# FX-50FHii_gameboy_Project.net
KiCad netlist of a schematic drawn in EasyEDA Pro
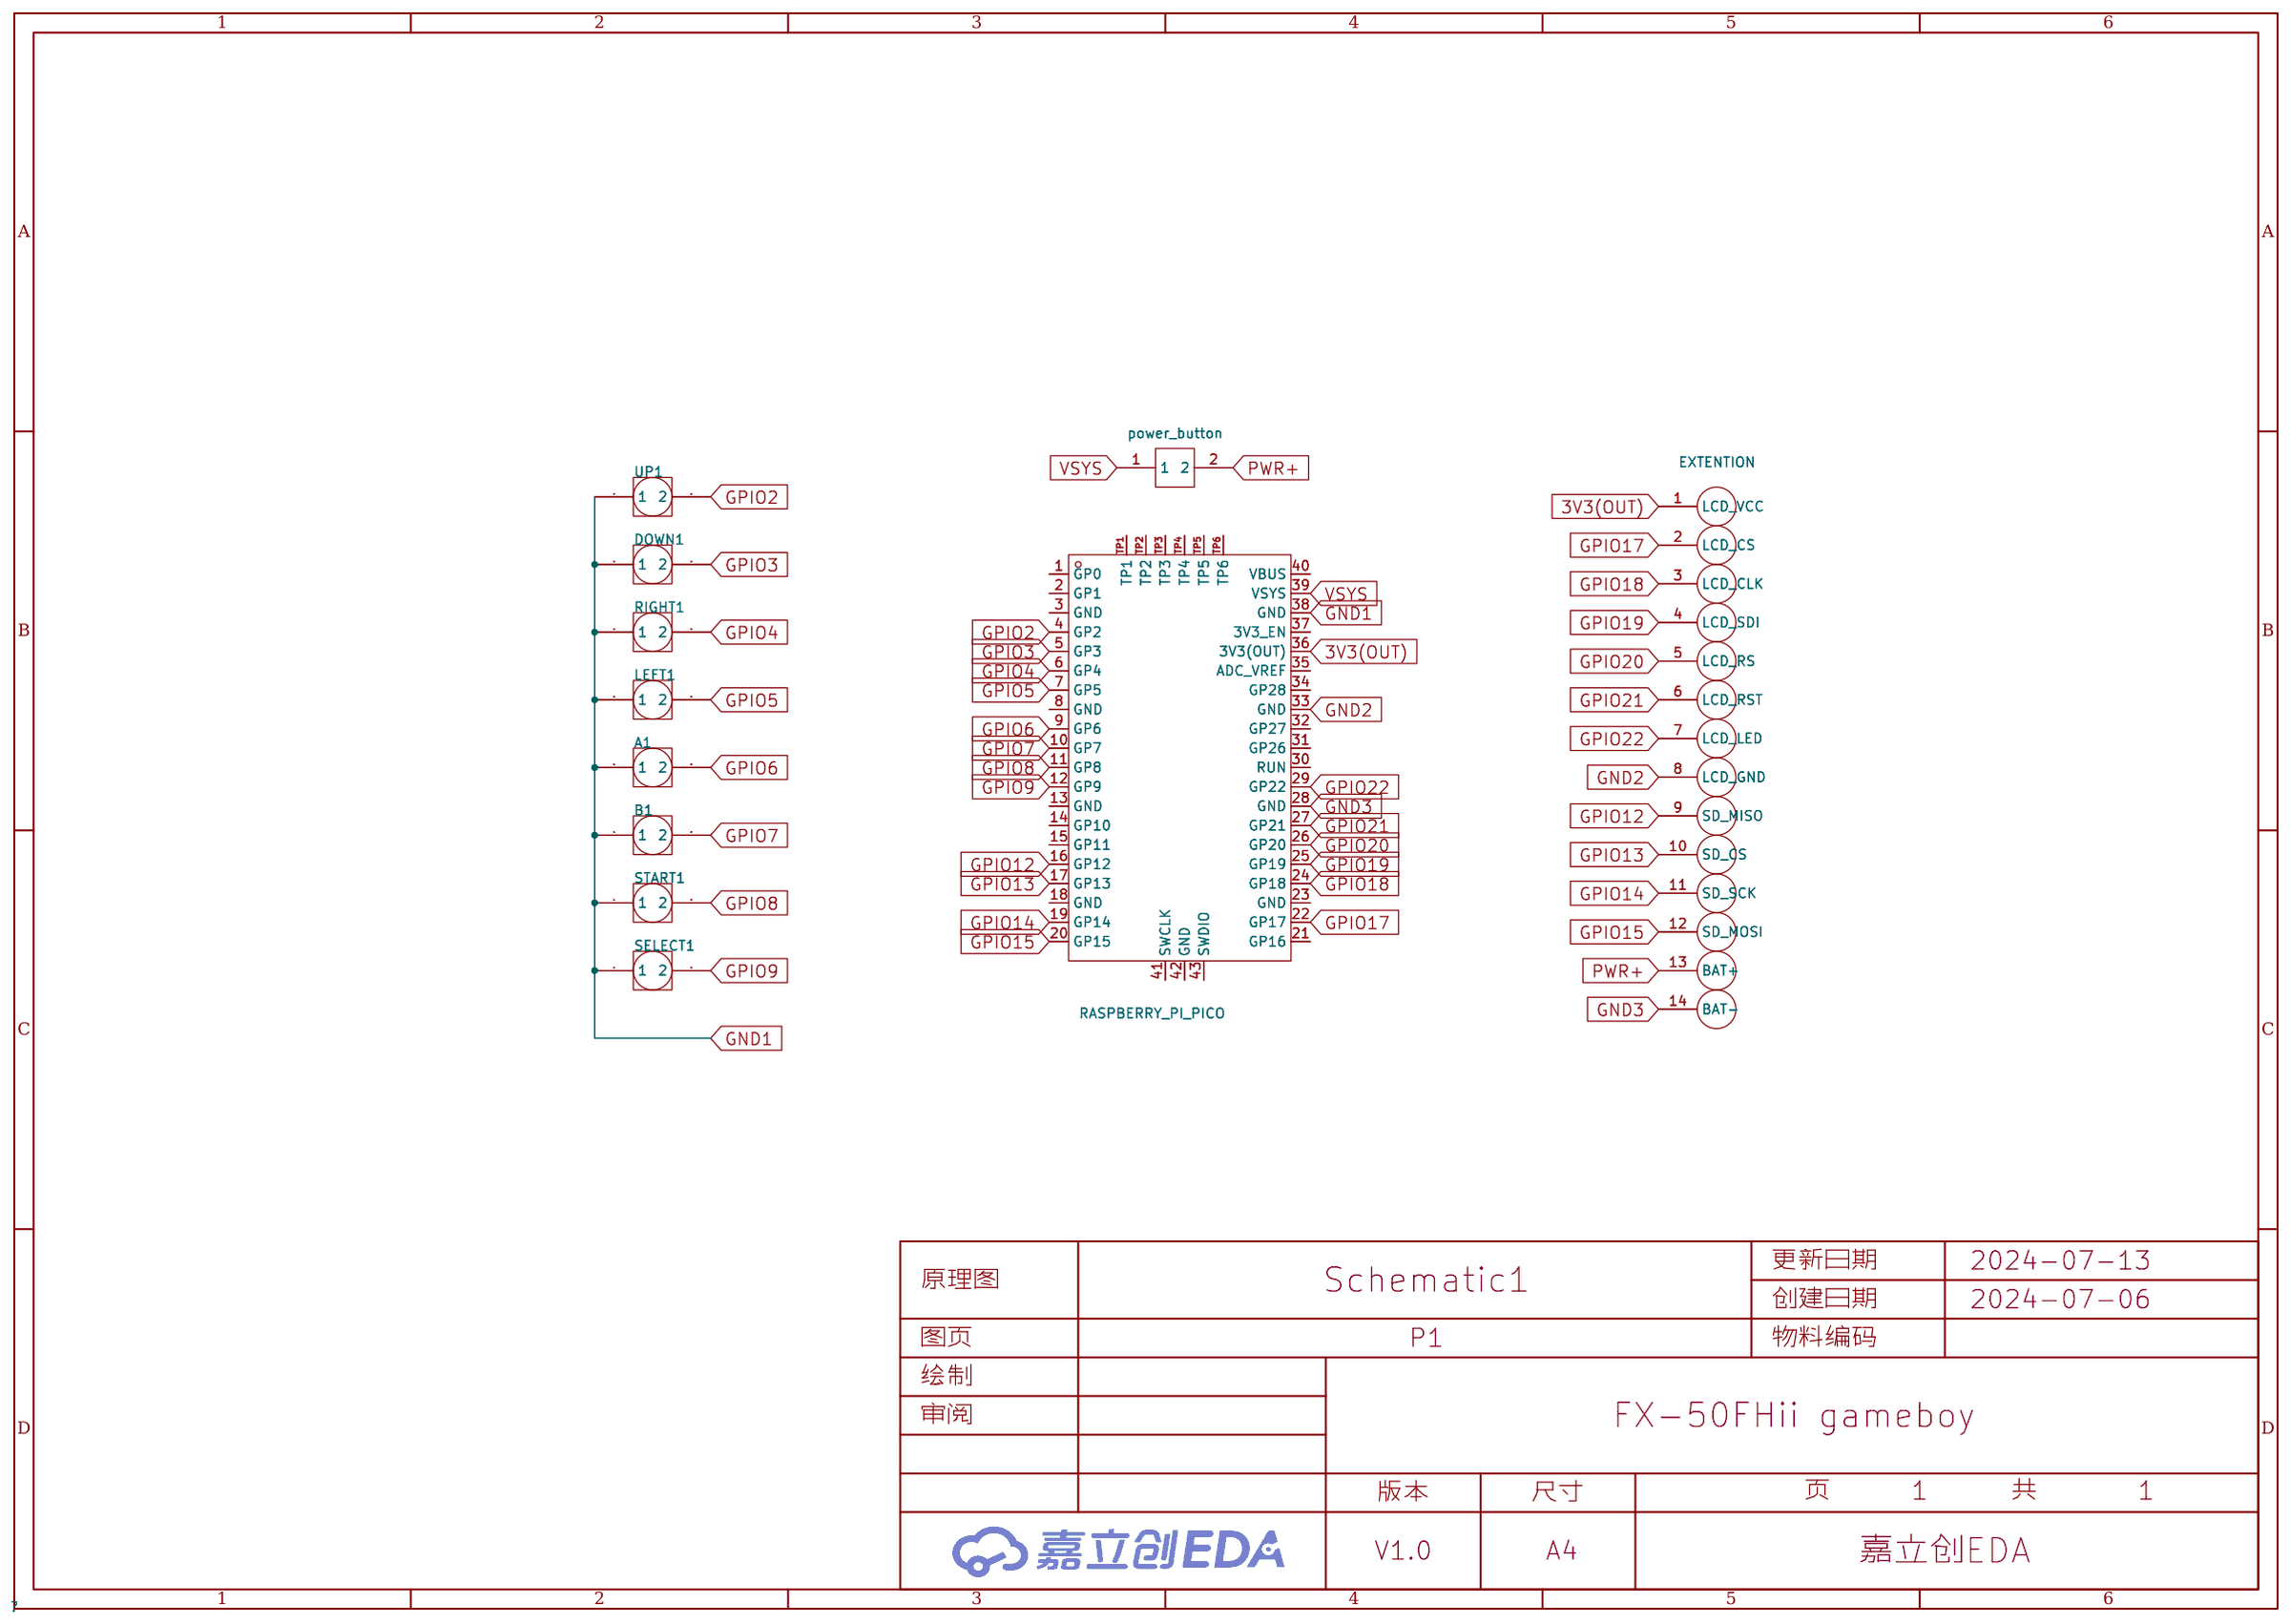
[diagram p0: schematic sheet]

(export (version "E")
  (design (tool "Eeschema 10.0.6"))
  (components
    (comp (ref "A1") (value "~") (footprint "easyedapro:锅仔按键") (libsource (lib "easyedapro") (part "导电胶触点")))
    (comp (ref "B1") (value "~") (footprint "easyedapro:锅仔按键") (libsource (lib "easyedapro") (part "导电胶触点")))
    (comp (ref "DOWN1")
      (value "~")
      (footprint "easyedapro:锅仔按键")
      (libsource (lib "easyedapro") (part "导电胶触点"))
    )
    (comp (ref "EXTENTION")
      (value "~")
      (footprint "easyedapro:CN1")
      (libsource (lib "easyedapro") (part "焊盤"))
    )
    (comp (ref "LEFT1")
      (value "~")
      (footprint "easyedapro:锅仔按键")
      (libsource (lib "easyedapro") (part "导电胶触点"))
    )
    (comp (ref "power_button")
      (value "~")
      (footprint "easyedapro:自動鎖住的按鈕")
      (libsource (lib "easyedapro") (part "自鎖按鈕"))
    )
    (comp (ref "RASPBERRY_PI_PICO")
      (value "~")
      (footprint "easyedapro:COMM-SMD_L51.0-W21.0-P2.54_SC0916")
      (libsource (lib "easyedapro") (part "PICO"))
    )
    (comp (ref "RIGHT1")
      (value "~")
      (footprint "easyedapro:锅仔按键")
      (libsource (lib "easyedapro") (part "导电胶触点"))
    )
    (comp (ref "SELECT1")
      (value "~")
      (footprint "easyedapro:锅仔按键")
      (libsource (lib "easyedapro") (part "导电胶触点"))
    )
    (comp (ref "START1")
      (value "~")
      (footprint "easyedapro:锅仔按键")
      (libsource (lib "easyedapro") (part "导电胶触点"))
    )
    (comp (ref "UP1") (value "~") (footprint "easyedapro:锅仔按键") (libsource (lib "easyedapro") (part "导电胶触点")))
  )
  (nets
    (net (code "1") (name "3V3(OUT)") (class "Default")
      (node (ref "EXTENTION") (pin "1") (pinfunction "LCD_VCC_1") (pintype "bidirectional"))
      (node (ref "RASPBERRY_PI_PICO") (pin "36") (pinfunction "3V3(OUT)_36") (pintype "unspecified"))
    )
    (net (code "2") (name "GND1") (class "Default")
      (node (ref "A1") (pin "1") (pinfunction "1_1") (pintype "input"))
      (node (ref "B1") (pin "1") (pinfunction "1_1") (pintype "input"))
      (node (ref "DOWN1") (pin "1") (pinfunction "1_1") (pintype "input"))
      (node (ref "LEFT1") (pin "1") (pinfunction "1_1") (pintype "input"))
      (node (ref "RASPBERRY_PI_PICO") (pin "38") (pinfunction "GND_38") (pintype "unspecified"))
      (node (ref "RIGHT1") (pin "1") (pinfunction "1_1") (pintype "input"))
      (node (ref "SELECT1") (pin "1") (pinfunction "1_1") (pintype "input"))
      (node (ref "START1") (pin "1") (pinfunction "1_1") (pintype "input"))
      (node (ref "UP1") (pin "1") (pinfunction "1_1") (pintype "input"))
    )
    (net (code "3") (name "GND2") (class "Default")
      (node (ref "EXTENTION") (pin "8") (pinfunction "LCD_GND_8") (pintype "bidirectional"))
      (node (ref "RASPBERRY_PI_PICO") (pin "33") (pinfunction "GND_33") (pintype "unspecified"))
    )
    (net (code "4") (name "GND3") (class "Default")
      (node (ref "EXTENTION") (pin "14") (pinfunction "BAT-_14") (pintype "bidirectional"))
      (node (ref "RASPBERRY_PI_PICO") (pin "28") (pinfunction "GND_28") (pintype "unspecified"))
    )
    (net (code "5") (name "GPIO2") (class "Default")
      (node (ref "RASPBERRY_PI_PICO") (pin "4") (pinfunction "GP2_4") (pintype "unspecified"))
      (node (ref "UP1") (pin "2") (pinfunction "2_2") (pintype "input"))
    )
    (net (code "6") (name "GPIO3") (class "Default")
      (node (ref "DOWN1") (pin "2") (pinfunction "2_2") (pintype "input"))
      (node (ref "RASPBERRY_PI_PICO") (pin "5") (pinfunction "GP3_5") (pintype "unspecified"))
    )
    (net (code "7") (name "GPIO4") (class "Default")
      (node (ref "RASPBERRY_PI_PICO") (pin "6") (pinfunction "GP4_6") (pintype "unspecified"))
      (node (ref "RIGHT1") (pin "2") (pinfunction "2_2") (pintype "input"))
    )
    (net (code "8") (name "GPIO5") (class "Default")
      (node (ref "LEFT1") (pin "2") (pinfunction "2_2") (pintype "input"))
      (node (ref "RASPBERRY_PI_PICO") (pin "7") (pinfunction "GP5_7") (pintype "unspecified"))
    )
    (net (code "9") (name "GPIO6") (class "Default")
      (node (ref "A1") (pin "2") (pinfunction "2_2") (pintype "input"))
      (node (ref "RASPBERRY_PI_PICO") (pin "9") (pinfunction "GP6_9") (pintype "unspecified"))
    )
    (net (code "10") (name "GPIO7") (class "Default")
      (node (ref "B1") (pin "2") (pinfunction "2_2") (pintype "input"))
      (node (ref "RASPBERRY_PI_PICO") (pin "10") (pinfunction "GP7_10") (pintype "unspecified"))
    )
    (net (code "11") (name "GPIO8") (class "Default")
      (node (ref "RASPBERRY_PI_PICO") (pin "11") (pinfunction "GP8_11") (pintype "unspecified"))
      (node (ref "START1") (pin "2") (pinfunction "2_2") (pintype "input"))
    )
    (net (code "12") (name "GPIO9") (class "Default")
      (node (ref "RASPBERRY_PI_PICO") (pin "12") (pinfunction "GP9_12") (pintype "unspecified"))
      (node (ref "SELECT1") (pin "2") (pinfunction "2_2") (pintype "input"))
    )
    (net (code "13") (name "GPIO12") (class "Default")
      (node (ref "EXTENTION") (pin "9") (pinfunction "SD_MISO_9") (pintype "bidirectional"))
      (node (ref "RASPBERRY_PI_PICO") (pin "16") (pinfunction "GP12_16") (pintype "unspecified"))
    )
    (net (code "14") (name "GPIO13") (class "Default")
      (node (ref "EXTENTION") (pin "10") (pinfunction "SD_CS_10") (pintype "bidirectional"))
      (node (ref "RASPBERRY_PI_PICO") (pin "17") (pinfunction "GP13_17") (pintype "unspecified"))
    )
    (net (code "15") (name "GPIO14") (class "Default")
      (node (ref "EXTENTION") (pin "11") (pinfunction "SD_SCK_11") (pintype "bidirectional"))
      (node (ref "RASPBERRY_PI_PICO") (pin "19") (pinfunction "GP14_19") (pintype "unspecified"))
    )
    (net (code "16") (name "GPIO15") (class "Default")
      (node (ref "EXTENTION") (pin "12") (pinfunction "SD_MOSI_12") (pintype "bidirectional"))
      (node (ref "RASPBERRY_PI_PICO") (pin "20") (pinfunction "GP15_20") (pintype "unspecified"))
    )
    (net (code "17") (name "GPIO17") (class "Default")
      (node (ref "EXTENTION") (pin "2") (pinfunction "LCD_CS_2") (pintype "bidirectional"))
      (node (ref "RASPBERRY_PI_PICO") (pin "22") (pinfunction "GP17_22") (pintype "unspecified"))
    )
    (net (code "18") (name "GPIO18") (class "Default")
      (node (ref "EXTENTION") (pin "3") (pinfunction "LCD_CLK_3") (pintype "bidirectional"))
      (node (ref "RASPBERRY_PI_PICO") (pin "24") (pinfunction "GP18_24") (pintype "unspecified"))
    )
    (net (code "19") (name "GPIO19") (class "Default")
      (node (ref "EXTENTION") (pin "4") (pinfunction "LCD_SDI_4") (pintype "bidirectional"))
      (node (ref "RASPBERRY_PI_PICO") (pin "25") (pinfunction "GP19_25") (pintype "unspecified"))
    )
    (net (code "20") (name "GPIO20") (class "Default")
      (node (ref "EXTENTION") (pin "5") (pinfunction "LCD_RS_5") (pintype "bidirectional"))
      (node (ref "RASPBERRY_PI_PICO") (pin "26") (pinfunction "GP20_26") (pintype "unspecified"))
    )
    (net (code "21") (name "GPIO21") (class "Default")
      (node (ref "EXTENTION") (pin "6") (pinfunction "LCD_RST_6") (pintype "bidirectional"))
      (node (ref "RASPBERRY_PI_PICO") (pin "27") (pinfunction "GP21_27") (pintype "unspecified"))
    )
    (net (code "22") (name "GPIO22") (class "Default")
      (node (ref "EXTENTION") (pin "7") (pinfunction "LCD_LED_7") (pintype "bidirectional"))
      (node (ref "RASPBERRY_PI_PICO") (pin "29") (pinfunction "GP22_29") (pintype "unspecified"))
    )
    (net (code "23") (name "PWR+") (class "Default")
      (node (ref "EXTENTION") (pin "13") (pinfunction "BAT+_13") (pintype "bidirectional"))
      (node (ref "power_button") (pin "2") (pinfunction "2_2") (pintype "input"))
    )
    (net (code "24") (name "VSYS") (class "Default")
      (node (ref "RASPBERRY_PI_PICO") (pin "39") (pinfunction "VSYS_39") (pintype "unspecified"))
      (node (ref "power_button") (pin "1") (pinfunction "1_1") (pintype "input"))
    )
    (net (code "25") (name "unconnected-(RASPBERRY_PI_PICO-3V3_EN-Pad37)") (class "Default")
      (node (ref "RASPBERRY_PI_PICO") (pin "37") (pinfunction "3V3_EN_37") (pintype "unspecified"))
    )
    (net (code "26") (name "unconnected-(RASPBERRY_PI_PICO-ADC_VREF-Pad35)") (class "Default")
      (node (ref "RASPBERRY_PI_PICO") (pin "35") (pinfunction "ADC_VREF_35") (pintype "unspecified"))
    )
    (net (code "27") (name "unconnected-(RASPBERRY_PI_PICO-GND-Pad3)") (class "Default")
      (node (ref "RASPBERRY_PI_PICO") (pin "3") (pinfunction "GND_3") (pintype "unspecified"))
    )
    (net (code "28") (name "unconnected-(RASPBERRY_PI_PICO-GND-Pad8)") (class "Default")
      (node (ref "RASPBERRY_PI_PICO") (pin "8") (pinfunction "GND_8") (pintype "unspecified"))
    )
    (net (code "29") (name "unconnected-(RASPBERRY_PI_PICO-GND-Pad13)") (class "Default")
      (node (ref "RASPBERRY_PI_PICO") (pin "13") (pinfunction "GND_13") (pintype "unspecified"))
    )
    (net (code "30") (name "unconnected-(RASPBERRY_PI_PICO-GND-Pad18)") (class "Default")
      (node (ref "RASPBERRY_PI_PICO") (pin "18") (pinfunction "GND_18") (pintype "unspecified"))
    )
    (net (code "31") (name "unconnected-(RASPBERRY_PI_PICO-GND-Pad23)") (class "Default")
      (node (ref "RASPBERRY_PI_PICO") (pin "23") (pinfunction "GND_23") (pintype "unspecified"))
    )
    (net (code "32") (name "unconnected-(RASPBERRY_PI_PICO-GND-Pad42)") (class "Default")
      (node (ref "RASPBERRY_PI_PICO") (pin "42") (pinfunction "GND_42") (pintype "unspecified"))
    )
    (net (code "33") (name "unconnected-(RASPBERRY_PI_PICO-GP0-Pad1)") (class "Default")
      (node (ref "RASPBERRY_PI_PICO") (pin "1") (pinfunction "GP0_1") (pintype "unspecified"))
    )
    (net (code "34") (name "unconnected-(RASPBERRY_PI_PICO-GP1-Pad2)") (class "Default")
      (node (ref "RASPBERRY_PI_PICO") (pin "2") (pinfunction "GP1_2") (pintype "unspecified"))
    )
    (net (code "35") (name "unconnected-(RASPBERRY_PI_PICO-GP10-Pad14)") (class "Default")
      (node (ref "RASPBERRY_PI_PICO") (pin "14") (pinfunction "GP10_14") (pintype "unspecified"))
    )
    (net (code "36") (name "unconnected-(RASPBERRY_PI_PICO-GP11-Pad15)") (class "Default")
      (node (ref "RASPBERRY_PI_PICO") (pin "15") (pinfunction "GP11_15") (pintype "unspecified"))
    )
    (net (code "37") (name "unconnected-(RASPBERRY_PI_PICO-GP16-Pad21)") (class "Default")
      (node (ref "RASPBERRY_PI_PICO") (pin "21") (pinfunction "GP16_21") (pintype "unspecified"))
    )
    (net (code "38") (name "unconnected-(RASPBERRY_PI_PICO-GP26-Pad31)") (class "Default")
      (node (ref "RASPBERRY_PI_PICO") (pin "31") (pinfunction "GP26_31") (pintype "unspecified"))
    )
    (net (code "39") (name "unconnected-(RASPBERRY_PI_PICO-GP27-Pad32)") (class "Default")
      (node (ref "RASPBERRY_PI_PICO") (pin "32") (pinfunction "GP27_32") (pintype "unspecified"))
    )
    (net (code "40") (name "unconnected-(RASPBERRY_PI_PICO-GP28-Pad34)") (class "Default")
      (node (ref "RASPBERRY_PI_PICO") (pin "34") (pinfunction "GP28_34") (pintype "unspecified"))
    )
    (net (code "41") (name "unconnected-(RASPBERRY_PI_PICO-PadTP1)") (class "Default")
      (node (ref "RASPBERRY_PI_PICO") (pin "TP1") (pinfunction "TP1_TP1") (pintype "unspecified"))
    )
    (net (code "42") (name "unconnected-(RASPBERRY_PI_PICO-PadTP2)") (class "Default")
      (node (ref "RASPBERRY_PI_PICO") (pin "TP2") (pinfunction "TP2_TP2") (pintype "unspecified"))
    )
    (net (code "43") (name "unconnected-(RASPBERRY_PI_PICO-PadTP3)") (class "Default")
      (node (ref "RASPBERRY_PI_PICO") (pin "TP3") (pinfunction "TP3_TP3") (pintype "unspecified"))
    )
    (net (code "44") (name "unconnected-(RASPBERRY_PI_PICO-PadTP4)") (class "Default")
      (node (ref "RASPBERRY_PI_PICO") (pin "TP4") (pinfunction "TP4_TP4") (pintype "unspecified"))
    )
    (net (code "45") (name "unconnected-(RASPBERRY_PI_PICO-PadTP5)") (class "Default")
      (node (ref "RASPBERRY_PI_PICO") (pin "TP5") (pinfunction "TP5_TP5") (pintype "unspecified"))
    )
    (net (code "46") (name "unconnected-(RASPBERRY_PI_PICO-PadTP6)") (class "Default")
      (node (ref "RASPBERRY_PI_PICO") (pin "TP6") (pinfunction "TP6_TP6") (pintype "unspecified"))
    )
    (net (code "47") (name "unconnected-(RASPBERRY_PI_PICO-RUN-Pad30)") (class "Default")
      (node (ref "RASPBERRY_PI_PICO") (pin "30") (pinfunction "RUN_30") (pintype "unspecified"))
    )
    (net (code "48") (name "unconnected-(RASPBERRY_PI_PICO-SWCLK-Pad41)") (class "Default")
      (node (ref "RASPBERRY_PI_PICO") (pin "41") (pinfunction "SWCLK_41") (pintype "unspecified"))
    )
    (net (code "49") (name "unconnected-(RASPBERRY_PI_PICO-SWDIO-Pad43)") (class "Default")
      (node (ref "RASPBERRY_PI_PICO") (pin "43") (pinfunction "SWDIO_43") (pintype "unspecified"))
    )
    (net (code "50") (name "unconnected-(RASPBERRY_PI_PICO-VBUS-Pad40)") (class "Default")
      (node (ref "RASPBERRY_PI_PICO") (pin "40") (pinfunction "VBUS_40") (pintype "unspecified"))
    )
  )
)
